# BlinkPico.net
KiCad netlist of a schematic drawn in Altium Designer
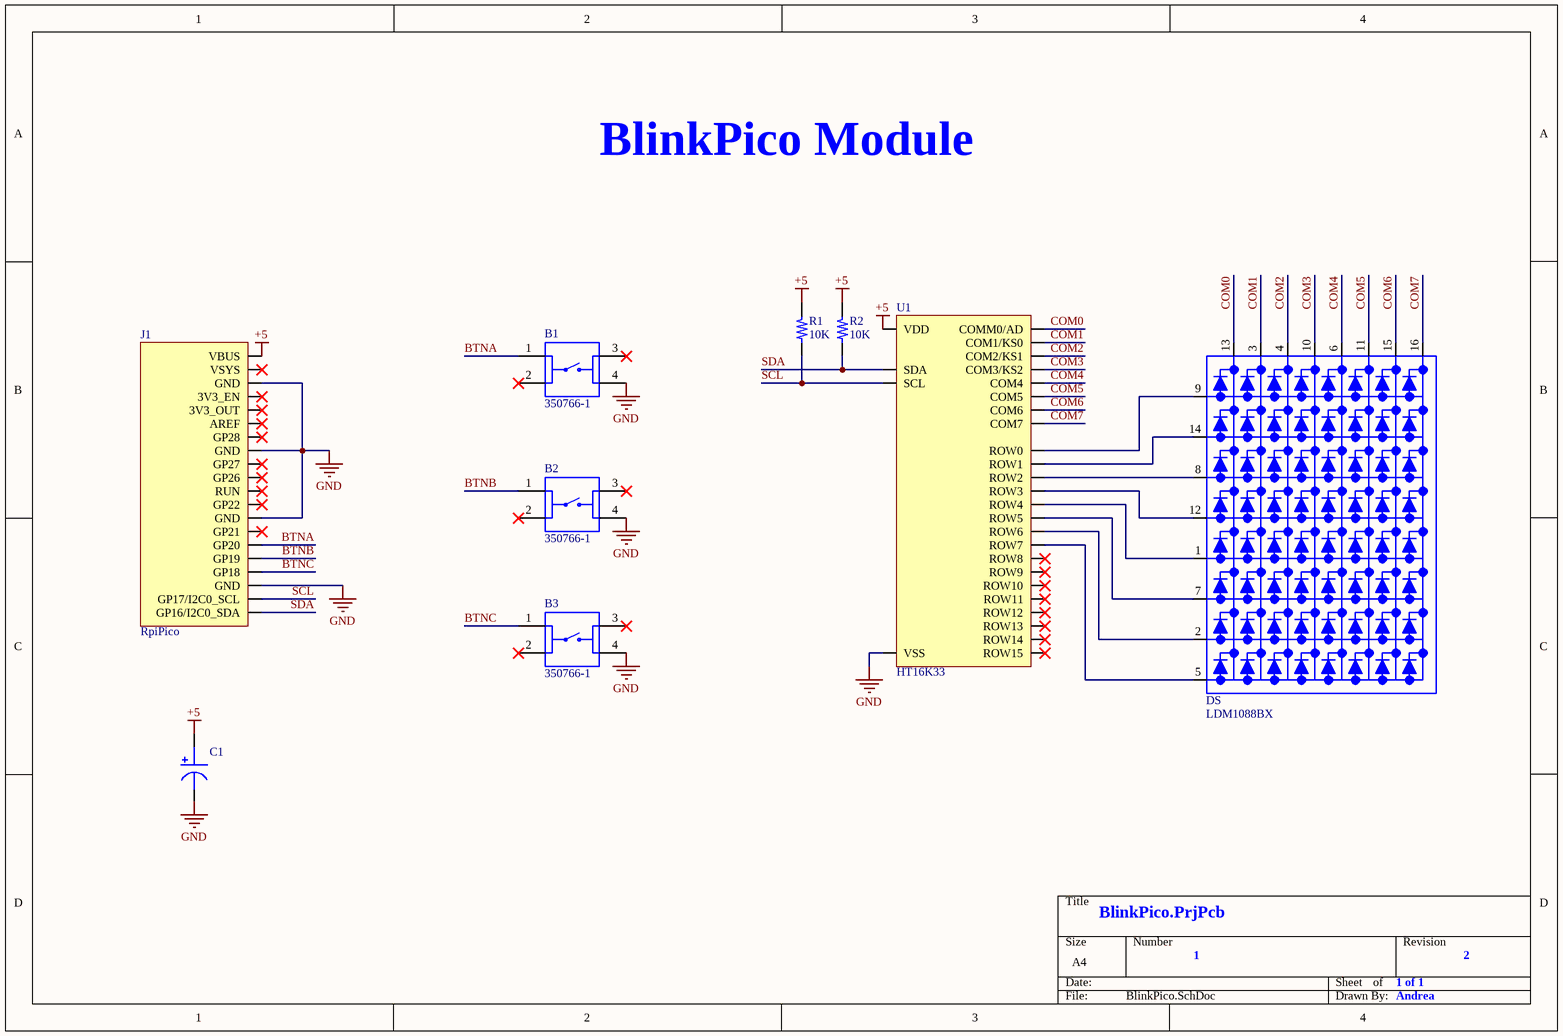
[diagram p0: BlinkPico.SchDoc]

(export (version "E")
  (design (tool "Eeschema 10.0.6"))
  (components
    (comp (ref "B1")
      (value "350766-1")
      (footprint "PUSH_BTN")
      (description "Connector, Soft Shell; Universal MATE-N-LOK; 3; Plug; Nylon; Natural; 19 A")
      (fields (field (name "MANUFACTURER") "TE Connectivity"))
      (libsource (lib "BlinkPico") (part "PUSH_BTN"))
    )
    (comp (ref "B2")
      (value "350766-1")
      (footprint "PUSH_BTN")
      (description "Connector, Soft Shell; Universal MATE-N-LOK; 3; Plug; Nylon; Natural; 19 A")
      (fields (field (name "MANUFACTURER") "TE Connectivity"))
      (libsource (lib "BlinkPico") (part "PUSH_BTN"))
    )
    (comp (ref "B3")
      (value "350766-1")
      (footprint "PUSH_BTN")
      (description "Connector, Soft Shell; Universal MATE-N-LOK; 3; Plug; Nylon; Natural; 19 A")
      (fields (field (name "MANUFACTURER") "TE Connectivity"))
      (libsource (lib "BlinkPico") (part "PUSH_BTN"))
    )
    (comp (ref "C1")
      (value "TCP1A106M8R")
      (footprint "C0805")
      (description "Cap Tant Solid 10uF 10V P CASE 20% (2 X 1.25 X 1.2mm) Inward L SMD 2012-12 125C T/R")
      (fields (field (name "MANUFACTURER") "Rohm") (field (name "TOLERANCE") "20%"))
      (libsource (lib "BlinkPico") (part "C0805_10U_TANTAL"))
    )
    (comp (ref "DS")
      (value "LDM1088BX")
      (footprint "LED_MATRIX_8X8")
      (description "DISPLAY, DOT MATRIX, 0.8, 8X8, GREEN; Display Dots x Lines: 8 x 8; LED Colour: Red")
      (fields (field (name "MF") "Kingbright") (field (name "MP") "TA08-81GWA"))
      (libsource (lib "BlinkPico") (part "LED_MATRIX"))
    )
    (comp (ref "J1")
      (value "RpiPico")
      (footprint "PICO_ADAPTER")
      (libsource (lib "BlinkPico") (part "PICO_ADAPTER"))
    )
    (comp (ref "R1")
      (value "10K")
      (footprint "R0805")
      (description "Res Thick Film 0805 10K Ohm 5% 1/8W ±100ppm/°C Molded SMD Paper T/R")
      (fields
        (field (name "MANUFACTURER") "Yageo")
        (field (name "MANUFACTURER PART NUMBER") "RC0805JR-0710KL")
      )
      (libsource (lib "BlinkPico") (part "R0805_10K"))
    )
    (comp (ref "R2")
      (value "10K")
      (footprint "R0805")
      (description "Res Thick Film 0805 10K Ohm 5% 1/8W ±100ppm/°C Molded SMD Paper T/R")
      (fields
        (field (name "MANUFACTURER") "Yageo")
        (field (name "MANUFACTURER PART NUMBER") "RC0805JR-0710KL")
      )
      (libsource (lib "BlinkPico") (part "R0805_10K"))
    )
    (comp (ref "U1") (value "HT16K33") (footprint "SOP28") (libsource (lib "BlinkPico") (part "HT16K33")))
  )
  (nets
    (net (code "1") (name "+5") (class "Default")
      (node (ref "C1") (pin "1") (pinfunction "1_1") (pintype "passive"))
      (node (ref "J1") (pin "1") (pinfunction "VBUS_1") (pintype "passive"))
      (node (ref "R1") (pin "2") (pinfunction "2_2") (pintype "passive"))
      (node (ref "R2") (pin "2") (pinfunction "2_2") (pintype "passive"))
      (node (ref "U1") (pin "28") (pinfunction "VDD_28") (pintype "passive"))
    )
    (net (code "2") (name "/BTNA") (class "Default")
      (node (ref "B1") (pin "1") (pinfunction "1_1") (pintype "passive"))
      (node (ref "J1") (pin "15") (pinfunction "GP20_15") (pintype "passive"))
    )
    (net (code "3") (name "/BTNB") (class "Default")
      (node (ref "B2") (pin "1") (pinfunction "1_1") (pintype "passive"))
      (node (ref "J1") (pin "16") (pinfunction "GP19_16") (pintype "passive"))
    )
    (net (code "4") (name "/BTNC") (class "Default")
      (node (ref "B3") (pin "1") (pinfunction "1_1") (pintype "passive"))
      (node (ref "J1") (pin "17") (pinfunction "GP18_17") (pintype "passive"))
    )
    (net (code "5") (name "/COM0") (class "Default")
      (node (ref "DS") (pin "13") (pinfunction "ANODE_COLUMN_1_13") (pintype "passive"))
      (node (ref "U1") (pin "2") (pinfunction "COMM0/AD_2") (pintype "passive"))
    )
    (net (code "6") (name "/COM1") (class "Default")
      (node (ref "DS") (pin "3") (pinfunction "ANODE_COLUMN_2_3") (pintype "passive"))
      (node (ref "U1") (pin "3") (pinfunction "COM1/KS0_3") (pintype "passive"))
    )
    (net (code "7") (name "/COM2") (class "Default")
      (node (ref "DS") (pin "4") (pinfunction "ANODE_COLUMN_3_4") (pintype "passive"))
      (node (ref "U1") (pin "4") (pinfunction "COM2/KS1_4") (pintype "passive"))
    )
    (net (code "8") (name "/COM3") (class "Default")
      (node (ref "DS") (pin "10") (pinfunction "ANODE_COLUMN_4_10") (pintype "passive"))
      (node (ref "U1") (pin "5") (pinfunction "COM3/KS2_5") (pintype "passive"))
    )
    (net (code "9") (name "/COM4") (class "Default")
      (node (ref "DS") (pin "6") (pinfunction "ANODE_COLUMN_5_6") (pintype "passive"))
      (node (ref "U1") (pin "6") (pinfunction "COM4_6") (pintype "passive"))
    )
    (net (code "10") (name "/COM5") (class "Default")
      (node (ref "DS") (pin "11") (pinfunction "ANODE_COLUMN_6_11") (pintype "passive"))
      (node (ref "U1") (pin "7") (pinfunction "COM5_7") (pintype "passive"))
    )
    (net (code "11") (name "/COM6") (class "Default")
      (node (ref "DS") (pin "15") (pinfunction "ANODE_COLUMN_7_15") (pintype "passive"))
      (node (ref "U1") (pin "8") (pinfunction "COM6_8") (pintype "passive"))
    )
    (net (code "12") (name "/COM7") (class "Default")
      (node (ref "DS") (pin "16") (pinfunction "ANODE_COLUMN_8_16") (pintype "passive"))
      (node (ref "U1") (pin "9") (pinfunction "COM7_9") (pintype "passive"))
    )
    (net (code "13") (name "/SCL") (class "Default")
      (node (ref "J1") (pin "19") (pinfunction "GP17/I2C0_SCL_19") (pintype "passive"))
      (node (ref "R1") (pin "1") (pinfunction "1_1") (pintype "passive"))
      (node (ref "U1") (pin "26") (pinfunction "SCL_26") (pintype "passive"))
    )
    (net (code "14") (name "/SDA") (class "Default")
      (node (ref "J1") (pin "20") (pinfunction "GP16/I2C0_SDA_20") (pintype "passive"))
      (node (ref "R2") (pin "1") (pinfunction "1_1") (pintype "passive"))
      (node (ref "U1") (pin "27") (pinfunction "SDA_27") (pintype "passive"))
    )
    (net (code "15") (name "GND") (class "Default")
      (node (ref "B1") (pin "4") (pinfunction "4_4") (pintype "passive"))
      (node (ref "B2") (pin "4") (pinfunction "4_4") (pintype "passive"))
      (node (ref "B3") (pin "4") (pinfunction "4_4") (pintype "passive"))
      (node (ref "C1") (pin "2") (pinfunction "2_2") (pintype "passive"))
      (node (ref "J1") (pin "13") (pinfunction "GND_13") (pintype "passive"))
      (node (ref "J1") (pin "18") (pinfunction "GND_18") (pintype "passive"))
      (node (ref "J1") (pin "3") (pinfunction "GND_3") (pintype "passive"))
      (node (ref "J1") (pin "8") (pinfunction "GND_8") (pintype "passive"))
      (node (ref "U1") (pin "1") (pinfunction "VSS_1") (pintype "passive"))
    )
    (net (code "16") (name "Net-(DS-CATHODE_ROW_1)") (class "Default")
      (node (ref "DS") (pin "9") (pinfunction "CATHODE_ROW_1_9") (pintype "passive"))
      (node (ref "U1") (pin "25") (pinfunction "ROW0_25") (pintype "passive"))
    )
    (net (code "17") (name "Net-(DS-CATHODE_ROW_2)") (class "Default")
      (node (ref "DS") (pin "14") (pinfunction "CATHODE_ROW_2_14") (pintype "passive"))
      (node (ref "U1") (pin "24") (pinfunction "ROW1_24") (pintype "passive"))
    )
    (net (code "18") (name "Net-(DS-CATHODE_ROW_3)") (class "Default")
      (node (ref "DS") (pin "8") (pinfunction "CATHODE_ROW_3_8") (pintype "passive"))
      (node (ref "U1") (pin "23") (pinfunction "ROW2_23") (pintype "passive"))
    )
    (net (code "19") (name "Net-(DS-CATHODE_ROW_4)") (class "Default")
      (node (ref "DS") (pin "12") (pinfunction "CATHODE_ROW_4_12") (pintype "passive"))
      (node (ref "U1") (pin "22") (pinfunction "ROW3_22") (pintype "passive"))
    )
    (net (code "20") (name "Net-(DS-CATHODE_ROW_5)") (class "Default")
      (node (ref "DS") (pin "1") (pinfunction "CATHODE_ROW_5_1") (pintype "passive"))
      (node (ref "U1") (pin "21") (pinfunction "ROW4_21") (pintype "passive"))
    )
    (net (code "21") (name "Net-(DS-CATHODE_ROW_6)") (class "Default")
      (node (ref "DS") (pin "7") (pinfunction "CATHODE_ROW_6_7") (pintype "passive"))
      (node (ref "U1") (pin "20") (pinfunction "ROW5_20") (pintype "passive"))
    )
    (net (code "22") (name "Net-(DS-CATHODE_ROW_7)") (class "Default")
      (node (ref "DS") (pin "2") (pinfunction "CATHODE_ROW_7_2") (pintype "passive"))
      (node (ref "U1") (pin "19") (pinfunction "ROW6_19") (pintype "passive"))
    )
    (net (code "23") (name "Net-(DS-CATHODE_ROW_8)") (class "Default")
      (node (ref "DS") (pin "5") (pinfunction "CATHODE_ROW_8_5") (pintype "passive"))
      (node (ref "U1") (pin "18") (pinfunction "ROW7_18") (pintype "passive"))
    )
    (net (code "24") (name "unconnected-(B1-Pad2)") (class "Default")
      (node (ref "B1") (pin "2") (pinfunction "2_2") (pintype "passive+no_connect"))
    )
    (net (code "25") (name "unconnected-(B1-Pad3)") (class "Default")
      (node (ref "B1") (pin "3") (pinfunction "3_3") (pintype "passive+no_connect"))
    )
    (net (code "26") (name "unconnected-(B2-Pad2)") (class "Default")
      (node (ref "B2") (pin "2") (pinfunction "2_2") (pintype "passive+no_connect"))
    )
    (net (code "27") (name "unconnected-(B2-Pad3)") (class "Default")
      (node (ref "B2") (pin "3") (pinfunction "3_3") (pintype "passive+no_connect"))
    )
    (net (code "28") (name "unconnected-(B3-Pad2)") (class "Default")
      (node (ref "B3") (pin "2") (pinfunction "2_2") (pintype "passive+no_connect"))
    )
    (net (code "29") (name "unconnected-(B3-Pad3)") (class "Default")
      (node (ref "B3") (pin "3") (pinfunction "3_3") (pintype "passive+no_connect"))
    )
    (net (code "30") (name "unconnected-(J1-3V3_EN-Pad4)") (class "Default")
      (node (ref "J1") (pin "4") (pinfunction "3V3_EN_4") (pintype "passive+no_connect"))
    )
    (net (code "31") (name "unconnected-(J1-3V3_OUT-Pad5)") (class "Default")
      (node (ref "J1") (pin "5") (pinfunction "3V3_OUT_5") (pintype "passive+no_connect"))
    )
    (net (code "32") (name "unconnected-(J1-AREF-Pad6)") (class "Default")
      (node (ref "J1") (pin "6") (pinfunction "AREF_6") (pintype "passive+no_connect"))
    )
    (net (code "33") (name "unconnected-(J1-GP21-Pad14)") (class "Default")
      (node (ref "J1") (pin "14") (pinfunction "GP21_14") (pintype "passive+no_connect"))
    )
    (net (code "34") (name "unconnected-(J1-GP22-Pad12)") (class "Default")
      (node (ref "J1") (pin "12") (pinfunction "GP22_12") (pintype "passive+no_connect"))
    )
    (net (code "35") (name "unconnected-(J1-GP26-Pad10)") (class "Default")
      (node (ref "J1") (pin "10") (pinfunction "GP26_10") (pintype "passive+no_connect"))
    )
    (net (code "36") (name "unconnected-(J1-GP27-Pad9)") (class "Default")
      (node (ref "J1") (pin "9") (pinfunction "GP27_9") (pintype "passive+no_connect"))
    )
    (net (code "37") (name "unconnected-(J1-GP28-Pad7)") (class "Default")
      (node (ref "J1") (pin "7") (pinfunction "GP28_7") (pintype "passive+no_connect"))
    )
    (net (code "38") (name "unconnected-(J1-RUN-Pad11)") (class "Default")
      (node (ref "J1") (pin "11") (pinfunction "RUN_11") (pintype "passive+no_connect"))
    )
    (net (code "39") (name "unconnected-(J1-VSYS-Pad2)") (class "Default")
      (node (ref "J1") (pin "2") (pinfunction "VSYS_2") (pintype "passive+no_connect"))
    )
    (net (code "40") (name "unconnected-(U1-ROW8-Pad17)") (class "Default")
      (node (ref "U1") (pin "17") (pinfunction "ROW8_17") (pintype "passive+no_connect"))
    )
    (net (code "41") (name "unconnected-(U1-ROW9-Pad16)") (class "Default")
      (node (ref "U1") (pin "16") (pinfunction "ROW9_16") (pintype "passive+no_connect"))
    )
    (net (code "42") (name "unconnected-(U1-ROW10-Pad15)") (class "Default")
      (node (ref "U1") (pin "15") (pinfunction "ROW10_15") (pintype "passive+no_connect"))
    )
    (net (code "43") (name "unconnected-(U1-ROW11-Pad14)") (class "Default")
      (node (ref "U1") (pin "14") (pinfunction "ROW11_14") (pintype "passive+no_connect"))
    )
    (net (code "44") (name "unconnected-(U1-ROW12-Pad13)") (class "Default")
      (node (ref "U1") (pin "13") (pinfunction "ROW12_13") (pintype "passive+no_connect"))
    )
    (net (code "45") (name "unconnected-(U1-ROW13-Pad12)") (class "Default")
      (node (ref "U1") (pin "12") (pinfunction "ROW13_12") (pintype "passive+no_connect"))
    )
    (net (code "46") (name "unconnected-(U1-ROW14-Pad11)") (class "Default")
      (node (ref "U1") (pin "11") (pinfunction "ROW14_11") (pintype "passive+no_connect"))
    )
    (net (code "47") (name "unconnected-(U1-ROW15-Pad10)") (class "Default")
      (node (ref "U1") (pin "10") (pinfunction "ROW15_10") (pintype "passive+no_connect"))
    )
  )
)
